# PC-DC_Board.net
KiCad netlist of a schematic drawn in EAGLE
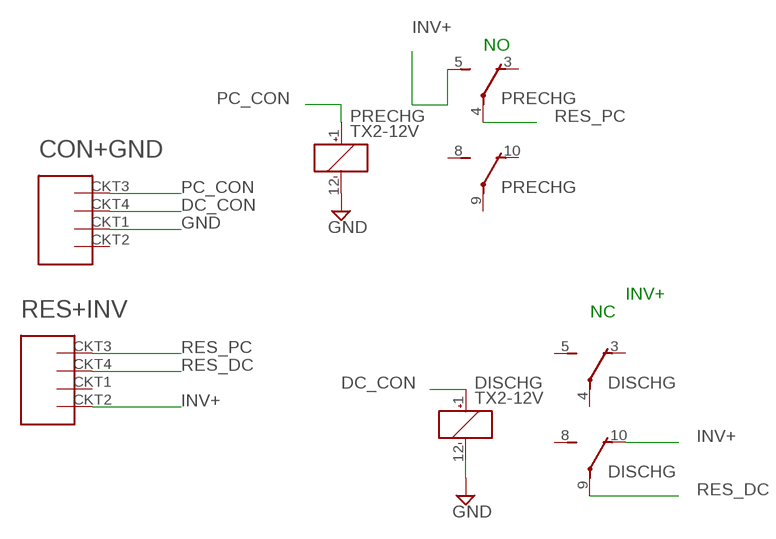
[diagram p0: schematic, sheet 1]

(export (version "E")
  (design (tool "Eeschema 10.0.6"))
  (components
    (comp (ref "CON+GND")
      (value "MHYBRIDMOLEX")
      (footprint "eagle-import:MOLEXMINIFIT6")
      (libsource (lib "eagle-import") (part "MHYBRIDMOLEX"))
    )
    (comp (ref "DISCHG")
      (value "TX2-12V")
      (footprint "eagle-import:TX2")
      (fields (field (name "MF") "AROMAT/ MATSUSHITA"))
      (libsource (lib "eagle-import") (part "TX2?-12V"))
    )
    (comp (ref "PRECHG")
      (value "TX2-12V")
      (footprint "eagle-import:TX2")
      (fields (field (name "MF") "AROMAT/ MATSUSHITA"))
      (libsource (lib "eagle-import") (part "TX2?-12V"))
    )
    (comp (ref "RES+INV")
      (value "MHYBRIDMOLEX")
      (footprint "eagle-import:MOLEXMINIFIT6")
      (libsource (lib "eagle-import") (part "MHYBRIDMOLEX"))
    )
  )
  (nets
    (net (code "1") (name "/DC_CON") (class "Default")
      (node (ref "CON+GND") (pin "CKT4") (pinfunction "V_IN2(12)_CKT4") (pintype "bidirectional"))
      (node (ref "DISCHG") (pin "1") (pinfunction "+_1") (pintype "passive"))
    )
    (net (code "2") (name "/INV+") (class "Default")
      (node (ref "DISCHG") (pin "10") (pinfunction "O_10") (pintype "passive"))
      (node (ref "PRECHG") (pin "5") (pinfunction "S_5") (pintype "passive"))
      (node (ref "RES+INV") (pin "CKT2") (pinfunction "GND2_CKT2") (pintype "bidirectional"))
    )
    (net (code "3") (name "/PC_CON") (class "Default")
      (node (ref "CON+GND") (pin "CKT3") (pinfunction "V_IN(12)_CKT3") (pintype "bidirectional"))
      (node (ref "PRECHG") (pin "1") (pinfunction "+_1") (pintype "passive"))
    )
    (net (code "4") (name "/RES_DC") (class "Default")
      (node (ref "DISCHG") (pin "9") (pinfunction "P_9") (pintype "passive"))
      (node (ref "RES+INV") (pin "CKT4") (pinfunction "V_IN2(12)_CKT4") (pintype "bidirectional"))
    )
    (net (code "5") (name "/RES_PC") (class "Default")
      (node (ref "PRECHG") (pin "4") (pinfunction "P_4") (pintype "passive"))
      (node (ref "RES+INV") (pin "CKT3") (pinfunction "V_IN(12)_CKT3") (pintype "bidirectional"))
    )
    (net (code "6") (name "GND") (class "Default")
      (node (ref "CON+GND") (pin "CKT1") (pinfunction "GND_CKT1") (pintype "bidirectional"))
      (node (ref "DISCHG") (pin "12") (pinfunction "-_12") (pintype "passive"))
      (node (ref "PRECHG") (pin "12") (pinfunction "-_12") (pintype "passive"))
    )
    (net (code "7") (name "unconnected-(CON+GND-GND2-PadCKT2)") (class "Default")
      (node (ref "CON+GND") (pin "CKT2") (pinfunction "GND2_CKT2") (pintype "bidirectional"))
    )
    (net (code "8") (name "unconnected-(DISCHGA-O-Pad3)") (class "Default")
      (node (ref "DISCHG") (pin "3") (pinfunction "O_3") (pintype "passive"))
    )
    (net (code "9") (name "unconnected-(DISCHGA-P-Pad4)") (class "Default")
      (node (ref "DISCHG") (pin "4") (pinfunction "P_4") (pintype "passive"))
    )
    (net (code "10") (name "unconnected-(DISCHGA-S-Pad5)") (class "Default")
      (node (ref "DISCHG") (pin "5") (pinfunction "S_5") (pintype "passive"))
    )
    (net (code "11") (name "unconnected-(DISCHGB-S-Pad8)") (class "Default")
      (node (ref "DISCHG") (pin "8") (pinfunction "S_8") (pintype "passive"))
    )
    (net (code "12") (name "unconnected-(PRECHGA-O-Pad3)") (class "Default")
      (node (ref "PRECHG") (pin "3") (pinfunction "O_3") (pintype "passive"))
    )
    (net (code "13") (name "unconnected-(PRECHGB-O-Pad10)") (class "Default")
      (node (ref "PRECHG") (pin "10") (pinfunction "O_10") (pintype "passive"))
    )
    (net (code "14") (name "unconnected-(PRECHGB-P-Pad9)") (class "Default")
      (node (ref "PRECHG") (pin "9") (pinfunction "P_9") (pintype "passive"))
    )
    (net (code "15") (name "unconnected-(PRECHGB-S-Pad8)") (class "Default")
      (node (ref "PRECHG") (pin "8") (pinfunction "S_8") (pintype "passive"))
    )
    (net (code "16") (name "unconnected-(RES+INV-GND-PadCKT1)") (class "Default")
      (node (ref "RES+INV") (pin "CKT1") (pinfunction "GND_CKT1") (pintype "bidirectional"))
    )
  )
)
